# M606A.net
KiCad netlist of a schematic drawn in EAGLE
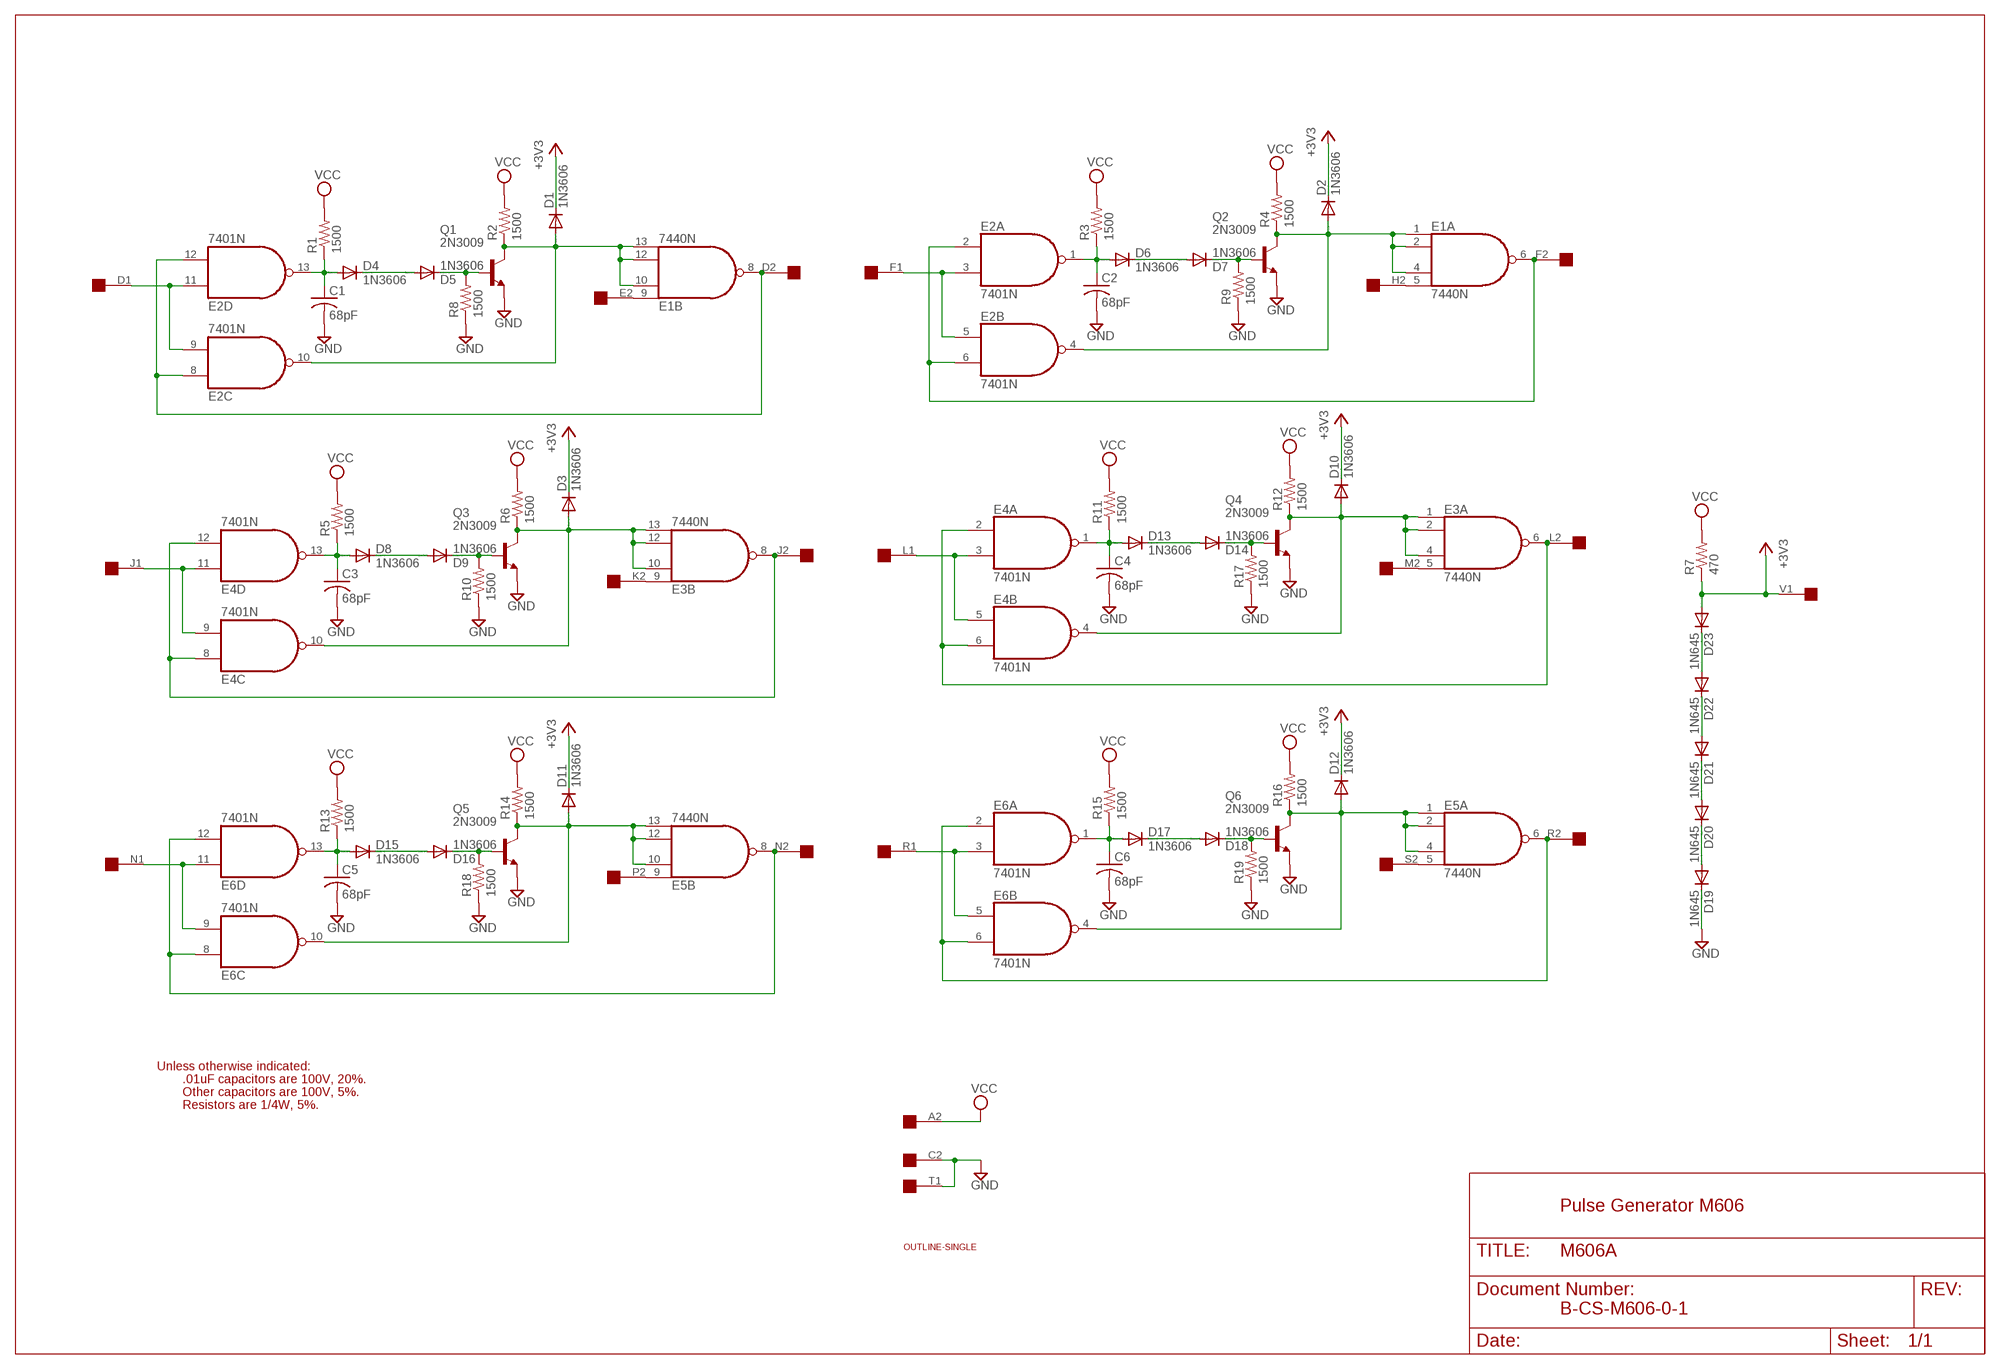
[diagram p0: schematic, sheet 1]

(export (version "E")
  (design (tool "Eeschema 10.0.6"))
  (components
    (comp (ref "C1")
      (value "68pF")
      (footprint "eagle-import:C075-032X103")
      (libsource (lib "eagle-import") (part "C-US075-032X103"))
    )
    (comp (ref "C2")
      (value "68pF")
      (footprint "eagle-import:C075-032X103")
      (libsource (lib "eagle-import") (part "C-US075-032X103"))
    )
    (comp (ref "C3")
      (value "68pF")
      (footprint "eagle-import:C075-032X103")
      (libsource (lib "eagle-import") (part "C-US075-032X103"))
    )
    (comp (ref "C4")
      (value "68pF")
      (footprint "eagle-import:C075-032X103")
      (libsource (lib "eagle-import") (part "C-US075-032X103"))
    )
    (comp (ref "C5")
      (value "68pF")
      (footprint "eagle-import:C075-032X103")
      (libsource (lib "eagle-import") (part "C-US075-032X103"))
    )
    (comp (ref "C6")
      (value "68pF")
      (footprint "eagle-import:C075-032X103")
      (libsource (lib "eagle-import") (part "C-US075-032X103"))
    )
    (comp (ref "D1")
      (value "1N3606")
      (footprint "eagle-import:DO35-10")
      (libsource (lib "eagle-import") (part "1N4148DO35-10"))
    )
    (comp (ref "D2")
      (value "1N3606")
      (footprint "eagle-import:DO35-10")
      (libsource (lib "eagle-import") (part "1N4148DO35-10"))
    )
    (comp (ref "D3")
      (value "1N3606")
      (footprint "eagle-import:DO35-10")
      (libsource (lib "eagle-import") (part "1N4148DO35-10"))
    )
    (comp (ref "D4")
      (value "1N3606")
      (footprint "eagle-import:DO35-10")
      (libsource (lib "eagle-import") (part "1N4148DO35-10"))
    )
    (comp (ref "D5")
      (value "1N3606")
      (footprint "eagle-import:DO35-10")
      (libsource (lib "eagle-import") (part "1N4148DO35-10"))
    )
    (comp (ref "D6")
      (value "1N3606")
      (footprint "eagle-import:DO35-10")
      (libsource (lib "eagle-import") (part "1N4148DO35-10"))
    )
    (comp (ref "D7")
      (value "1N3606")
      (footprint "eagle-import:DO35-10")
      (libsource (lib "eagle-import") (part "1N4148DO35-10"))
    )
    (comp (ref "D8")
      (value "1N3606")
      (footprint "eagle-import:DO35-10")
      (libsource (lib "eagle-import") (part "1N4148DO35-10"))
    )
    (comp (ref "D9")
      (value "1N3606")
      (footprint "eagle-import:DO35-10")
      (libsource (lib "eagle-import") (part "1N4148DO35-10"))
    )
    (comp (ref "D10")
      (value "1N3606")
      (footprint "eagle-import:DO35-10")
      (libsource (lib "eagle-import") (part "1N4148DO35-10"))
    )
    (comp (ref "D11")
      (value "1N3606")
      (footprint "eagle-import:DO35-10")
      (libsource (lib "eagle-import") (part "1N4148DO35-10"))
    )
    (comp (ref "D12")
      (value "1N3606")
      (footprint "eagle-import:DO35-10")
      (libsource (lib "eagle-import") (part "1N4148DO35-10"))
    )
    (comp (ref "D13")
      (value "1N3606")
      (footprint "eagle-import:DO35-10")
      (libsource (lib "eagle-import") (part "1N4148DO35-10"))
    )
    (comp (ref "D14")
      (value "1N3606")
      (footprint "eagle-import:DO35-10")
      (libsource (lib "eagle-import") (part "1N4148DO35-10"))
    )
    (comp (ref "D15")
      (value "1N3606")
      (footprint "eagle-import:DO35-10")
      (libsource (lib "eagle-import") (part "1N4148DO35-10"))
    )
    (comp (ref "D16")
      (value "1N3606")
      (footprint "eagle-import:DO35-10")
      (libsource (lib "eagle-import") (part "1N4148DO35-10"))
    )
    (comp (ref "D17")
      (value "1N3606")
      (footprint "eagle-import:DO35-10")
      (libsource (lib "eagle-import") (part "1N4148DO35-10"))
    )
    (comp (ref "D18")
      (value "1N3606")
      (footprint "eagle-import:DO35-10")
      (libsource (lib "eagle-import") (part "1N4148DO35-10"))
    )
    (comp (ref "D19")
      (value "1N645")
      (footprint "eagle-import:DO35-10")
      (libsource (lib "eagle-import") (part "1N4148DO35-10"))
    )
    (comp (ref "D20")
      (value "1N645")
      (footprint "eagle-import:DO35-10")
      (libsource (lib "eagle-import") (part "1N4148DO35-10"))
    )
    (comp (ref "D21")
      (value "1N645")
      (footprint "eagle-import:DO35-10")
      (libsource (lib "eagle-import") (part "1N4148DO35-10"))
    )
    (comp (ref "D22")
      (value "1N645")
      (footprint "eagle-import:DO35-10")
      (libsource (lib "eagle-import") (part "1N4148DO35-10"))
    )
    (comp (ref "D23")
      (value "1N645")
      (footprint "eagle-import:DO35-10")
      (libsource (lib "eagle-import") (part "1N4148DO35-10"))
    )
    (comp (ref "E1")
      (value "7440N")
      (footprint "eagle-import:DIL14")
      (libsource (lib "eagle-import") (part "7420NS"))
    )
    (comp (ref "E2")
      (value "7401N")
      (footprint "eagle-import:DIL14")
      (libsource (lib "eagle-import") (part "7401NLS"))
    )
    (comp (ref "E3")
      (value "7440N")
      (footprint "eagle-import:DIL14")
      (libsource (lib "eagle-import") (part "7420NS"))
    )
    (comp (ref "E4")
      (value "7401N")
      (footprint "eagle-import:DIL14")
      (libsource (lib "eagle-import") (part "7401NLS"))
    )
    (comp (ref "E5")
      (value "7440N")
      (footprint "eagle-import:DIL14")
      (libsource (lib "eagle-import") (part "7420NS"))
    )
    (comp (ref "E6")
      (value "7401N")
      (footprint "eagle-import:DIL14")
      (libsource (lib "eagle-import") (part "7401NLS"))
    )
    (comp (ref "Q1")
      (value "2N3009")
      (footprint "eagle-import:TO39")
      (libsource (lib "eagle-import") (part "2N3019"))
    )
    (comp (ref "Q2")
      (value "2N3009")
      (footprint "eagle-import:TO39")
      (libsource (lib "eagle-import") (part "2N3019"))
    )
    (comp (ref "Q3")
      (value "2N3009")
      (footprint "eagle-import:TO39")
      (libsource (lib "eagle-import") (part "2N3019"))
    )
    (comp (ref "Q4")
      (value "2N3009")
      (footprint "eagle-import:TO39")
      (libsource (lib "eagle-import") (part "2N3019"))
    )
    (comp (ref "Q5")
      (value "2N3009")
      (footprint "eagle-import:TO39")
      (libsource (lib "eagle-import") (part "2N3019"))
    )
    (comp (ref "Q6")
      (value "2N3009")
      (footprint "eagle-import:TO39")
      (libsource (lib "eagle-import") (part "2N3019"))
    )
    (comp (ref "R1")
      (value "1500")
      (footprint "eagle-import:0207_10")
      (libsource (lib "eagle-import") (part "R-US_0207/10"))
    )
    (comp (ref "R2")
      (value "1500")
      (footprint "eagle-import:0207_10")
      (libsource (lib "eagle-import") (part "R-US_0207/10"))
    )
    (comp (ref "R3")
      (value "1500")
      (footprint "eagle-import:0207_10")
      (libsource (lib "eagle-import") (part "R-US_0207/10"))
    )
    (comp (ref "R4")
      (value "1500")
      (footprint "eagle-import:0207_10")
      (libsource (lib "eagle-import") (part "R-US_0207/10"))
    )
    (comp (ref "R5")
      (value "1500")
      (footprint "eagle-import:0207_10")
      (libsource (lib "eagle-import") (part "R-US_0207/10"))
    )
    (comp (ref "R6")
      (value "1500")
      (footprint "eagle-import:0207_10")
      (libsource (lib "eagle-import") (part "R-US_0207/10"))
    )
    (comp (ref "R7")
      (value "470")
      (footprint "eagle-import:0207_10")
      (libsource (lib "eagle-import") (part "R-US_0207/10"))
    )
    (comp (ref "R8")
      (value "1500")
      (footprint "eagle-import:0207_10")
      (libsource (lib "eagle-import") (part "R-US_0207/10"))
    )
    (comp (ref "R9")
      (value "1500")
      (footprint "eagle-import:0207_10")
      (libsource (lib "eagle-import") (part "R-US_0207/10"))
    )
    (comp (ref "R10")
      (value "1500")
      (footprint "eagle-import:0207_10")
      (libsource (lib "eagle-import") (part "R-US_0207/10"))
    )
    (comp (ref "R11")
      (value "1500")
      (footprint "eagle-import:0207_10")
      (libsource (lib "eagle-import") (part "R-US_0207/10"))
    )
    (comp (ref "R12")
      (value "1500")
      (footprint "eagle-import:0207_10")
      (libsource (lib "eagle-import") (part "R-US_0207/10"))
    )
    (comp (ref "R13")
      (value "1500")
      (footprint "eagle-import:0207_10")
      (libsource (lib "eagle-import") (part "R-US_0207/10"))
    )
    (comp (ref "R14")
      (value "1500")
      (footprint "eagle-import:0207_10")
      (libsource (lib "eagle-import") (part "R-US_0207/10"))
    )
    (comp (ref "R15")
      (value "1500")
      (footprint "eagle-import:0207_10")
      (libsource (lib "eagle-import") (part "R-US_0207/10"))
    )
    (comp (ref "R16")
      (value "1500")
      (footprint "eagle-import:0207_10")
      (libsource (lib "eagle-import") (part "R-US_0207/10"))
    )
    (comp (ref "R17")
      (value "1500")
      (footprint "eagle-import:0207_10")
      (libsource (lib "eagle-import") (part "R-US_0207/10"))
    )
    (comp (ref "R18")
      (value "1500")
      (footprint "eagle-import:0207_10")
      (libsource (lib "eagle-import") (part "R-US_0207/10"))
    )
    (comp (ref "R19")
      (value "1500")
      (footprint "eagle-import:0207_10")
      (libsource (lib "eagle-import") (part "R-US_0207/10"))
    )
    (comp (ref "U$2")
      (value "SINGLE")
      (footprint "eagle-import:EDGE-CON2")
      (libsource (lib "eagle-import") (part "SINGLE"))
    )
    (comp (ref "U$4")
      (value "OUTLINE-SINGLE")
      (footprint "eagle-import:SINGLE")
      (libsource (lib "eagle-import") (part "OUTLINE-SINGLE"))
    )
  )
  (nets
    (net (code "1") (name "+3V3") (class "Default")
      (node (ref "D1") (pin "C") (pinfunction "C_C") (pintype "passive"))
      (node (ref "D10") (pin "C") (pinfunction "C_C") (pintype "passive"))
      (node (ref "D11") (pin "C") (pinfunction "C_C") (pintype "passive"))
      (node (ref "D12") (pin "C") (pinfunction "C_C") (pintype "passive"))
      (node (ref "D2") (pin "C") (pinfunction "C_C") (pintype "passive"))
      (node (ref "D23") (pin "A") (pinfunction "A_A") (pintype "passive"))
      (node (ref "D3") (pin "C") (pinfunction "C_C") (pintype "passive"))
      (node (ref "R7") (pin "1") (pinfunction "1_1") (pintype "passive"))
      (node (ref "U$2") (pin "V1") (pinfunction "1_V1") (pintype "bidirectional"))
    )
    (net (code "2") (name "GND") (class "Default")
      (node (ref "C1") (pin "2") (pinfunction "2_2") (pintype "passive"))
      (node (ref "C2") (pin "2") (pinfunction "2_2") (pintype "passive"))
      (node (ref "C3") (pin "2") (pinfunction "2_2") (pintype "passive"))
      (node (ref "C4") (pin "2") (pinfunction "2_2") (pintype "passive"))
      (node (ref "C5") (pin "2") (pinfunction "2_2") (pintype "passive"))
      (node (ref "C6") (pin "2") (pinfunction "2_2") (pintype "passive"))
      (node (ref "D19") (pin "C") (pinfunction "C_C") (pintype "passive"))
      (node (ref "Q1") (pin "1") (pinfunction "E_1") (pintype "passive"))
      (node (ref "Q2") (pin "1") (pinfunction "E_1") (pintype "passive"))
      (node (ref "Q3") (pin "1") (pinfunction "E_1") (pintype "passive"))
      (node (ref "Q4") (pin "1") (pinfunction "E_1") (pintype "passive"))
      (node (ref "Q5") (pin "1") (pinfunction "E_1") (pintype "passive"))
      (node (ref "Q6") (pin "1") (pinfunction "E_1") (pintype "passive"))
      (node (ref "R10") (pin "1") (pinfunction "1_1") (pintype "passive"))
      (node (ref "R17") (pin "1") (pinfunction "1_1") (pintype "passive"))
      (node (ref "R18") (pin "1") (pinfunction "1_1") (pintype "passive"))
      (node (ref "R19") (pin "1") (pinfunction "1_1") (pintype "passive"))
      (node (ref "R8") (pin "1") (pinfunction "1_1") (pintype "passive"))
      (node (ref "R9") (pin "1") (pinfunction "1_1") (pintype "passive"))
      (node (ref "U$2") (pin "C2") (pinfunction "1_C2") (pintype "bidirectional"))
      (node (ref "U$2") (pin "T1") (pinfunction "1_T1") (pintype "bidirectional"))
    )
    (net (code "3") (name "Net-(D4-PadC)") (class "Default")
      (node (ref "D4") (pin "C") (pinfunction "C_C") (pintype "passive"))
      (node (ref "D5") (pin "A") (pinfunction "A_A") (pintype "passive"))
    )
    (net (code "4") (name "Net-(D6-PadC)") (class "Default")
      (node (ref "D6") (pin "C") (pinfunction "C_C") (pintype "passive"))
      (node (ref "D7") (pin "A") (pinfunction "A_A") (pintype "passive"))
    )
    (net (code "5") (name "Net-(D8-PadC)") (class "Default")
      (node (ref "D8") (pin "C") (pinfunction "C_C") (pintype "passive"))
      (node (ref "D9") (pin "A") (pinfunction "A_A") (pintype "passive"))
    )
    (net (code "6") (name "Net-(D13-PadC)") (class "Default")
      (node (ref "D13") (pin "C") (pinfunction "C_C") (pintype "passive"))
      (node (ref "D14") (pin "A") (pinfunction "A_A") (pintype "passive"))
    )
    (net (code "7") (name "Net-(D15-PadC)") (class "Default")
      (node (ref "D15") (pin "C") (pinfunction "C_C") (pintype "passive"))
      (node (ref "D16") (pin "A") (pinfunction "A_A") (pintype "passive"))
    )
    (net (code "8") (name "Net-(D17-PadC)") (class "Default")
      (node (ref "D17") (pin "C") (pinfunction "C_C") (pintype "passive"))
      (node (ref "D18") (pin "A") (pinfunction "A_A") (pintype "passive"))
    )
    (net (code "9") (name "Net-(D19-PadA)") (class "Default")
      (node (ref "D19") (pin "A") (pinfunction "A_A") (pintype "passive"))
      (node (ref "D20") (pin "C") (pinfunction "C_C") (pintype "passive"))
    )
    (net (code "10") (name "Net-(D20-PadA)") (class "Default")
      (node (ref "D20") (pin "A") (pinfunction "A_A") (pintype "passive"))
      (node (ref "D21") (pin "C") (pinfunction "C_C") (pintype "passive"))
    )
    (net (code "11") (name "Net-(D21-PadA)") (class "Default")
      (node (ref "D21") (pin "A") (pinfunction "A_A") (pintype "passive"))
      (node (ref "D22") (pin "C") (pinfunction "C_C") (pintype "passive"))
    )
    (net (code "12") (name "Net-(D22-PadA)") (class "Default")
      (node (ref "D22") (pin "A") (pinfunction "A_A") (pintype "passive"))
      (node (ref "D23") (pin "C") (pinfunction "C_C") (pintype "passive"))
    )
    (net (code "13") (name "Net-(E1A-I0)") (class "Default")
      (node (ref "D2") (pin "A") (pinfunction "A_A") (pintype "passive"))
      (node (ref "E1") (pin "1") (pinfunction "I0_1") (pintype "input"))
      (node (ref "E1") (pin "2") (pinfunction "I1_2") (pintype "input"))
      (node (ref "E1") (pin "4") (pinfunction "I2_4") (pintype "input"))
      (node (ref "E2") (pin "4") (pinfunction "O_4") (pintype "open_collector"))
      (node (ref "Q2") (pin "3") (pinfunction "C_3") (pintype "passive"))
      (node (ref "R4") (pin "1") (pinfunction "1_1") (pintype "passive"))
    )
    (net (code "14") (name "Net-(E1A-I3)") (class "Default")
      (node (ref "E1") (pin "5") (pinfunction "I3_5") (pintype "input"))
      (node (ref "U$2") (pin "H2") (pinfunction "1_H2") (pintype "bidirectional"))
    )
    (net (code "15") (name "Net-(E1A-O)") (class "Default")
      (node (ref "E1") (pin "6") (pinfunction "O_6") (pintype "output"))
      (node (ref "E2") (pin "2") (pinfunction "I0_2") (pintype "input"))
      (node (ref "E2") (pin "6") (pinfunction "I1_6") (pintype "input"))
      (node (ref "U$2") (pin "F2") (pinfunction "1_F2") (pintype "bidirectional"))
    )
    (net (code "16") (name "Net-(E1B-I0)") (class "Default")
      (node (ref "E1") (pin "9") (pinfunction "I0_9") (pintype "input"))
      (node (ref "U$2") (pin "E2") (pinfunction "1_E2") (pintype "bidirectional"))
    )
    (net (code "17") (name "Net-(E1B-I1)") (class "Default")
      (node (ref "D1") (pin "A") (pinfunction "A_A") (pintype "passive"))
      (node (ref "E1") (pin "10") (pinfunction "I1_10") (pintype "input"))
      (node (ref "E1") (pin "12") (pinfunction "I2_12") (pintype "input"))
      (node (ref "E1") (pin "13") (pinfunction "I3_13") (pintype "input"))
      (node (ref "E2") (pin "10") (pinfunction "O_10") (pintype "open_collector"))
      (node (ref "Q1") (pin "3") (pinfunction "C_3") (pintype "passive"))
      (node (ref "R2") (pin "1") (pinfunction "1_1") (pintype "passive"))
    )
    (net (code "18") (name "Net-(E1B-O)") (class "Default")
      (node (ref "E1") (pin "8") (pinfunction "O_8") (pintype "output"))
      (node (ref "E2") (pin "12") (pinfunction "I1_12") (pintype "input"))
      (node (ref "E2") (pin "8") (pinfunction "I0_8") (pintype "input"))
      (node (ref "U$2") (pin "D2") (pinfunction "1_D2") (pintype "bidirectional"))
    )
    (net (code "19") (name "Net-(E2A-I1)") (class "Default")
      (node (ref "E2") (pin "3") (pinfunction "I1_3") (pintype "input"))
      (node (ref "E2") (pin "5") (pinfunction "I0_5") (pintype "input"))
      (node (ref "U$2") (pin "F1") (pinfunction "1_F1") (pintype "bidirectional"))
    )
    (net (code "20") (name "Net-(E2A-O)") (class "Default")
      (node (ref "C2") (pin "1") (pinfunction "1_1") (pintype "passive"))
      (node (ref "D6") (pin "A") (pinfunction "A_A") (pintype "passive"))
      (node (ref "E2") (pin "1") (pinfunction "O_1") (pintype "open_collector"))
      (node (ref "R3") (pin "1") (pinfunction "1_1") (pintype "passive"))
    )
    (net (code "21") (name "Net-(E2C-I1)") (class "Default")
      (node (ref "E2") (pin "11") (pinfunction "I0_11") (pintype "input"))
      (node (ref "E2") (pin "9") (pinfunction "I1_9") (pintype "input"))
      (node (ref "U$2") (pin "D1") (pinfunction "1_D1") (pintype "bidirectional"))
    )
    (net (code "22") (name "Net-(E2D-O)") (class "Default")
      (node (ref "C1") (pin "1") (pinfunction "1_1") (pintype "passive"))
      (node (ref "D4") (pin "A") (pinfunction "A_A") (pintype "passive"))
      (node (ref "E2") (pin "13") (pinfunction "O_13") (pintype "open_collector"))
      (node (ref "R1") (pin "1") (pinfunction "1_1") (pintype "passive"))
    )
    (net (code "23") (name "Net-(E3A-I0)") (class "Default")
      (node (ref "D10") (pin "A") (pinfunction "A_A") (pintype "passive"))
      (node (ref "E3") (pin "1") (pinfunction "I0_1") (pintype "input"))
      (node (ref "E3") (pin "2") (pinfunction "I1_2") (pintype "input"))
      (node (ref "E3") (pin "4") (pinfunction "I2_4") (pintype "input"))
      (node (ref "E4") (pin "4") (pinfunction "O_4") (pintype "open_collector"))
      (node (ref "Q4") (pin "3") (pinfunction "C_3") (pintype "passive"))
      (node (ref "R12") (pin "1") (pinfunction "1_1") (pintype "passive"))
    )
    (net (code "24") (name "Net-(E3A-I3)") (class "Default")
      (node (ref "E3") (pin "5") (pinfunction "I3_5") (pintype "input"))
      (node (ref "U$2") (pin "M2") (pinfunction "1_M2") (pintype "bidirectional"))
    )
    (net (code "25") (name "Net-(E3A-O)") (class "Default")
      (node (ref "E3") (pin "6") (pinfunction "O_6") (pintype "output"))
      (node (ref "E4") (pin "2") (pinfunction "I0_2") (pintype "input"))
      (node (ref "E4") (pin "6") (pinfunction "I1_6") (pintype "input"))
      (node (ref "U$2") (pin "L2") (pinfunction "1_L2") (pintype "bidirectional"))
    )
    (net (code "26") (name "Net-(E3B-I0)") (class "Default")
      (node (ref "E3") (pin "9") (pinfunction "I0_9") (pintype "input"))
      (node (ref "U$2") (pin "K2") (pinfunction "1_K2") (pintype "bidirectional"))
    )
    (net (code "27") (name "Net-(E3B-I1)") (class "Default")
      (node (ref "D3") (pin "A") (pinfunction "A_A") (pintype "passive"))
      (node (ref "E3") (pin "10") (pinfunction "I1_10") (pintype "input"))
      (node (ref "E3") (pin "12") (pinfunction "I2_12") (pintype "input"))
      (node (ref "E3") (pin "13") (pinfunction "I3_13") (pintype "input"))
      (node (ref "E4") (pin "10") (pinfunction "O_10") (pintype "open_collector"))
      (node (ref "Q3") (pin "3") (pinfunction "C_3") (pintype "passive"))
      (node (ref "R6") (pin "1") (pinfunction "1_1") (pintype "passive"))
    )
    (net (code "28") (name "Net-(E3B-O)") (class "Default")
      (node (ref "E3") (pin "8") (pinfunction "O_8") (pintype "output"))
      (node (ref "E4") (pin "12") (pinfunction "I1_12") (pintype "input"))
      (node (ref "E4") (pin "8") (pinfunction "I0_8") (pintype "input"))
      (node (ref "U$2") (pin "J2") (pinfunction "1_J2") (pintype "bidirectional"))
    )
    (net (code "29") (name "Net-(E4A-I1)") (class "Default")
      (node (ref "E4") (pin "3") (pinfunction "I1_3") (pintype "input"))
      (node (ref "E4") (pin "5") (pinfunction "I0_5") (pintype "input"))
      (node (ref "U$2") (pin "L1") (pinfunction "1_L1") (pintype "bidirectional"))
    )
    (net (code "30") (name "Net-(E4A-O)") (class "Default")
      (node (ref "C4") (pin "1") (pinfunction "1_1") (pintype "passive"))
      (node (ref "D13") (pin "A") (pinfunction "A_A") (pintype "passive"))
      (node (ref "E4") (pin "1") (pinfunction "O_1") (pintype "open_collector"))
      (node (ref "R11") (pin "1") (pinfunction "1_1") (pintype "passive"))
    )
    (net (code "31") (name "Net-(E4C-I1)") (class "Default")
      (node (ref "E4") (pin "11") (pinfunction "I0_11") (pintype "input"))
      (node (ref "E4") (pin "9") (pinfunction "I1_9") (pintype "input"))
      (node (ref "U$2") (pin "J1") (pinfunction "1_J1") (pintype "bidirectional"))
    )
    (net (code "32") (name "Net-(E4D-O)") (class "Default")
      (node (ref "C3") (pin "1") (pinfunction "1_1") (pintype "passive"))
      (node (ref "D8") (pin "A") (pinfunction "A_A") (pintype "passive"))
      (node (ref "E4") (pin "13") (pinfunction "O_13") (pintype "open_collector"))
      (node (ref "R5") (pin "1") (pinfunction "1_1") (pintype "passive"))
    )
    (net (code "33") (name "Net-(E5A-I0)") (class "Default")
      (node (ref "D12") (pin "A") (pinfunction "A_A") (pintype "passive"))
      (node (ref "E5") (pin "1") (pinfunction "I0_1") (pintype "input"))
      (node (ref "E5") (pin "2") (pinfunction "I1_2") (pintype "input"))
      (node (ref "E5") (pin "4") (pinfunction "I2_4") (pintype "input"))
      (node (ref "E6") (pin "4") (pinfunction "O_4") (pintype "open_collector"))
      (node (ref "Q6") (pin "3") (pinfunction "C_3") (pintype "passive"))
      (node (ref "R16") (pin "1") (pinfunction "1_1") (pintype "passive"))
    )
    (net (code "34") (name "Net-(E5A-I3)") (class "Default")
      (node (ref "E5") (pin "5") (pinfunction "I3_5") (pintype "input"))
      (node (ref "U$2") (pin "S2") (pinfunction "1_S2") (pintype "bidirectional"))
    )
    (net (code "35") (name "Net-(E5A-O)") (class "Default")
      (node (ref "E5") (pin "6") (pinfunction "O_6") (pintype "output"))
      (node (ref "E6") (pin "2") (pinfunction "I0_2") (pintype "input"))
      (node (ref "E6") (pin "6") (pinfunction "I1_6") (pintype "input"))
      (node (ref "U$2") (pin "R2") (pinfunction "1_R2") (pintype "bidirectional"))
    )
    (net (code "36") (name "Net-(E5B-I0)") (class "Default")
      (node (ref "E5") (pin "9") (pinfunction "I0_9") (pintype "input"))
      (node (ref "U$2") (pin "P2") (pinfunction "1_P2") (pintype "bidirectional"))
    )
    (net (code "37") (name "Net-(E5B-I1)") (class "Default")
      (node (ref "D11") (pin "A") (pinfunction "A_A") (pintype "passive"))
      (node (ref "E5") (pin "10") (pinfunction "I1_10") (pintype "input"))
      (node (ref "E5") (pin "12") (pinfunction "I2_12") (pintype "input"))
      (node (ref "E5") (pin "13") (pinfunction "I3_13") (pintype "input"))
      (node (ref "E6") (pin "10") (pinfunction "O_10") (pintype "open_collector"))
      (node (ref "Q5") (pin "3") (pinfunction "C_3") (pintype "passive"))
      (node (ref "R14") (pin "1") (pinfunction "1_1") (pintype "passive"))
    )
    (net (code "38") (name "Net-(E5B-O)") (class "Default")
      (node (ref "E5") (pin "8") (pinfunction "O_8") (pintype "output"))
      (node (ref "E6") (pin "12") (pinfunction "I1_12") (pintype "input"))
      (node (ref "E6") (pin "8") (pinfunction "I0_8") (pintype "input"))
      (node (ref "U$2") (pin "N2") (pinfunction "1_N2") (pintype "bidirectional"))
    )
    (net (code "39") (name "Net-(E6A-I1)") (class "Default")
      (node (ref "E6") (pin "3") (pinfunction "I1_3") (pintype "input"))
      (node (ref "E6") (pin "5") (pinfunction "I0_5") (pintype "input"))
      (node (ref "U$2") (pin "R1") (pinfunction "1_R1") (pintype "bidirectional"))
    )
    (net (code "40") (name "Net-(E6A-O)") (class "Default")
      (node (ref "C6") (pin "1") (pinfunction "1_1") (pintype "passive"))
      (node (ref "D17") (pin "A") (pinfunction "A_A") (pintype "passive"))
      (node (ref "E6") (pin "1") (pinfunction "O_1") (pintype "open_collector"))
      (node (ref "R15") (pin "1") (pinfunction "1_1") (pintype "passive"))
    )
    (net (code "41") (name "Net-(E6C-I1)") (class "Default")
      (node (ref "E6") (pin "11") (pinfunction "I0_11") (pintype "input"))
      (node (ref "E6") (pin "9") (pinfunction "I1_9") (pintype "input"))
      (node (ref "U$2") (pin "N1") (pinfunction "1_N1") (pintype "bidirectional"))
    )
    (net (code "42") (name "Net-(E6D-O)") (class "Default")
      (node (ref "C5") (pin "1") (pinfunction "1_1") (pintype "passive"))
      (node (ref "D15") (pin "A") (pinfunction "A_A") (pintype "passive"))
      (node (ref "E6") (pin "13") (pinfunction "O_13") (pintype "open_collector"))
      (node (ref "R13") (pin "1") (pinfunction "1_1") (pintype "passive"))
    )
    (net (code "43") (name "Net-(Q1-B)") (class "Default")
      (node (ref "D5") (pin "C") (pinfunction "C_C") (pintype "passive"))
      (node (ref "Q1") (pin "2") (pinfunction "B_2") (pintype "passive"))
      (node (ref "R8") (pin "2") (pinfunction "2_2") (pintype "passive"))
    )
    (net (code "44") (name "Net-(Q2-B)") (class "Default")
      (node (ref "D7") (pin "C") (pinfunction "C_C") (pintype "passive"))
      (node (ref "Q2") (pin "2") (pinfunction "B_2") (pintype "passive"))
      (node (ref "R9") (pin "2") (pinfunction "2_2") (pintype "passive"))
    )
    (net (code "45") (name "Net-(Q3-B)") (class "Default")
      (node (ref "D9") (pin "C") (pinfunction "C_C") (pintype "passive"))
      (node (ref "Q3") (pin "2") (pinfunction "B_2") (pintype "passive"))
      (node (ref "R10") (pin "2") (pinfunction "2_2") (pintype "passive"))
    )
    (net (code "46") (name "Net-(Q4-B)") (class "Default")
      (node (ref "D14") (pin "C") (pinfunction "C_C") (pintype "passive"))
      (node (ref "Q4") (pin "2") (pinfunction "B_2") (pintype "passive"))
      (node (ref "R17") (pin "2") (pinfunction "2_2") (pintype "passive"))
    )
    (net (code "47") (name "Net-(Q5-B)") (class "Default")
      (node (ref "D16") (pin "C") (pinfunction "C_C") (pintype "passive"))
      (node (ref "Q5") (pin "2") (pinfunction "B_2") (pintype "passive"))
      (node (ref "R18") (pin "2") (pinfunction "2_2") (pintype "passive"))
    )
    (net (code "48") (name "Net-(Q6-B)") (class "Default")
      (node (ref "D18") (pin "C") (pinfunction "C_C") (pintype "passive"))
      (node (ref "Q6") (pin "2") (pinfunction "B_2") (pintype "passive"))
      (node (ref "R19") (pin "2") (pinfunction "2_2") (pintype "passive"))
    )
    (net (code "49") (name "VCC") (class "Default")
      (node (ref "R1") (pin "2") (pinfunction "2_2") (pintype "passive"))
      (node (ref "R11") (pin "2") (pinfunction "2_2") (pintype "passive"))
      (node (ref "R12") (pin "2") (pinfunction "2_2") (pintype "passive"))
      (node (ref "R13") (pin "2") (pinfunction "2_2") (pintype "passive"))
      (node (ref "R14") (pin "2") (pinfunction "2_2") (pintype "passive"))
      (node (ref "R15") (pin "2") (pinfunction "2_2") (pintype "passive"))
      (node (ref "R16") (pin "2") (pinfunction "2_2") (pintype "passive"))
      (node (ref "R2") (pin "2") (pinfunction "2_2") (pintype "passive"))
      (node (ref "R3") (pin "2") (pinfunction "2_2") (pintype "passive"))
      (node (ref "R4") (pin "2") (pinfunction "2_2") (pintype "passive"))
      (node (ref "R5") (pin "2") (pinfunction "2_2") (pintype "passive"))
      (node (ref "R6") (pin "2") (pinfunction "2_2") (pintype "passive"))
      (node (ref "R7") (pin "2") (pinfunction "2_2") (pintype "passive"))
      (node (ref "U$2") (pin "A2") (pinfunction "1_A2") (pintype "bidirectional"))
    )
  )
)
